# Port_Expander.net
KiCad netlist of a schematic drawn in Altium Designer
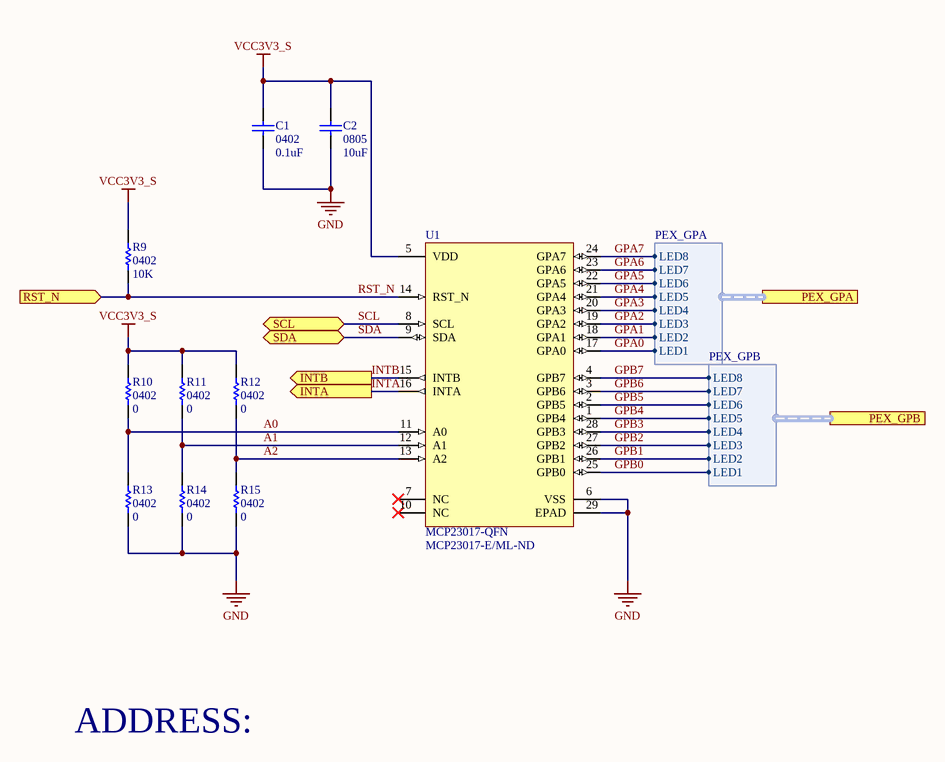
[diagram p0: Port Expander.SchDoc]

(export (version "E")
  (design (tool "Eeschema 10.0.6"))
  (components
    (comp (ref "C1")
      (value "0402")
      (footprint "CAP0402R")
      (description "0402 capacitor")
      (fields
        (field (name "ALTIUM_VALUE") "0.1uF")
        (field (name "MANUFACTURER") "Taiyo Yuden")
        (field (name "MANUFACTURER PART NUMBER") "EMK105B7104KVHF")
      )
      (libsource (lib "heron-general") (part "CAP0402"))
    )
    (comp (ref "C2")
      (value "0805")
      (footprint "CAP0805R")
      (description "0805 capacitor")
      (fields
        (field (name "ALTIUM_VALUE") "10uF")
        (field (name "MANUFACTURER") "Murata")
        (field (name "MANUFACTURER PART NUMBER") "GCM21BR70J106KE22K")
      )
      (libsource (lib "heron-general") (part "CAP0805"))
    )
    (comp (ref "R9")
      (value "0402")
      (footprint "RES0402R")
      (description "0402 resistor")
      (fields
        (field (name "ALTIUM_VALUE") "10K")
        (field (name "MANUFACTURER") "Panasonic")
        (field (name "MANUFACTURER PART NUMBER") "ERJ-2RKF1002X")
      )
      (libsource (lib "heron-general") (part "RES0402"))
    )
    (comp (ref "R10")
      (value "0402")
      (footprint "RES0402R")
      (description "0402 resistor")
      (fields
        (field (name "ALTIUM_VALUE") "0")
        (field (name "MANUFACTURER") "Panasonic")
        (field (name "MANUFACTURER PART NUMBER") "ERJ-2GE0R00X")
      )
      (libsource (lib "heron-general") (part "RES0402"))
    )
    (comp (ref "R11")
      (value "0402")
      (footprint "RES0402R")
      (description "0402 resistor")
      (fields
        (field (name "ALTIUM_VALUE") "0")
        (field (name "MANUFACTURER") "Panasonic")
        (field (name "MANUFACTURER PART NUMBER") "ERJ-2GE0R00X")
      )
      (libsource (lib "heron-general") (part "RES0402"))
    )
    (comp (ref "R12")
      (value "0402")
      (footprint "RES0402R")
      (description "0402 resistor")
      (fields
        (field (name "ALTIUM_VALUE") "0")
        (field (name "MANUFACTURER") "Panasonic")
        (field (name "MANUFACTURER PART NUMBER") "ERJ-2GE0R00X")
      )
      (libsource (lib "heron-general") (part "RES0402"))
    )
    (comp (ref "R13")
      (value "0402")
      (footprint "RES0402R")
      (description "0402 resistor")
      (fields
        (field (name "ALTIUM_VALUE") "0")
        (field (name "MANUFACTURER") "Panasonic")
        (field (name "MANUFACTURER PART NUMBER") "ERJ-2GE0R00X")
      )
      (libsource (lib "heron-general") (part "RES0402"))
    )
    (comp (ref "R14")
      (value "0402")
      (footprint "RES0402R")
      (description "0402 resistor")
      (fields
        (field (name "ALTIUM_VALUE") "0")
        (field (name "MANUFACTURER") "Panasonic")
        (field (name "MANUFACTURER PART NUMBER") "ERJ-2GE0R00X")
      )
      (libsource (lib "heron-general") (part "RES0402"))
    )
    (comp (ref "R15")
      (value "0402")
      (footprint "RES0402R")
      (description "0402 resistor")
      (fields
        (field (name "ALTIUM_VALUE") "0")
        (field (name "MANUFACTURER") "Panasonic")
        (field (name "MANUFACTURER PART NUMBER") "ERJ-2GE0R00X")
      )
      (libsource (lib "heron-general") (part "RES0402"))
    )
    (comp (ref "U1")
      (value "MCP23017-QFN")
      (footprint "QFN65P600X600X100-29")
      (fields (field (name "SUPPLIER PART NUMBER 1") "MCP23017-E/ML-ND"))
      (libsource (lib "heron-general") (part "MCP23017-QFN"))
    )
  )
  (nets
    (net (code "3") (name "/A0") (class "Default")
      (node (ref "R10") (pin "1") (pinfunction "1_1") (pintype "passive"))
      (node (ref "R13") (pin "2") (pinfunction "2_2") (pintype "passive"))
      (node (ref "U1") (pin "11") (pinfunction "A0_11") (pintype "input"))
    )
    (net (code "4") (name "/A1") (class "Default")
      (node (ref "R11") (pin "1") (pinfunction "1_1") (pintype "passive"))
      (node (ref "R14") (pin "2") (pinfunction "2_2") (pintype "passive"))
      (node (ref "U1") (pin "12") (pinfunction "A1_12") (pintype "input"))
    )
    (net (code "5") (name "/A2") (class "Default")
      (node (ref "R12") (pin "1") (pinfunction "1_1") (pintype "passive"))
      (node (ref "R15") (pin "2") (pinfunction "2_2") (pintype "passive"))
      (node (ref "U1") (pin "13") (pinfunction "A2_13") (pintype "input"))
    )
    (net (code "6") (name "/GPA0") (class "Default")
      (node (ref "U1") (pin "17") (pinfunction "GPA0_17") (pintype "bidirectional"))
    )
    (net (code "7") (name "/GPA1") (class "Default")
      (node (ref "U1") (pin "18") (pinfunction "GPA1_18") (pintype "bidirectional"))
    )
    (net (code "8") (name "/GPA2") (class "Default")
      (node (ref "U1") (pin "19") (pinfunction "GPA2_19") (pintype "bidirectional"))
    )
    (net (code "9") (name "/GPA3") (class "Default")
      (node (ref "U1") (pin "20") (pinfunction "GPA3_20") (pintype "bidirectional"))
    )
    (net (code "10") (name "/GPA4") (class "Default")
      (node (ref "U1") (pin "21") (pinfunction "GPA4_21") (pintype "bidirectional"))
    )
    (net (code "11") (name "/GPA5") (class "Default")
      (node (ref "U1") (pin "22") (pinfunction "GPA5_22") (pintype "bidirectional"))
    )
    (net (code "12") (name "/GPA6") (class "Default")
      (node (ref "U1") (pin "23") (pinfunction "GPA6_23") (pintype "bidirectional"))
    )
    (net (code "13") (name "/GPA7") (class "Default")
      (node (ref "U1") (pin "24") (pinfunction "GPA7_24") (pintype "bidirectional"))
    )
    (net (code "14") (name "/GPB0") (class "Default")
      (node (ref "U1") (pin "25") (pinfunction "GPB0_25") (pintype "bidirectional"))
    )
    (net (code "15") (name "/GPB1") (class "Default")
      (node (ref "U1") (pin "26") (pinfunction "GPB1_26") (pintype "bidirectional"))
    )
    (net (code "16") (name "/GPB2") (class "Default")
      (node (ref "U1") (pin "27") (pinfunction "GPB2_27") (pintype "bidirectional"))
    )
    (net (code "17") (name "/GPB3") (class "Default")
      (node (ref "U1") (pin "28") (pinfunction "GPB3_28") (pintype "bidirectional"))
    )
    (net (code "18") (name "/GPB4") (class "Default")
      (node (ref "U1") (pin "1") (pinfunction "GPB4_1") (pintype "bidirectional"))
    )
    (net (code "19") (name "/GPB5") (class "Default")
      (node (ref "U1") (pin "2") (pinfunction "GPB5_2") (pintype "bidirectional"))
    )
    (net (code "20") (name "/GPB6") (class "Default")
      (node (ref "U1") (pin "3") (pinfunction "GPB6_3") (pintype "bidirectional"))
    )
    (net (code "21") (name "/GPB7") (class "Default")
      (node (ref "U1") (pin "4") (pinfunction "GPB7_4") (pintype "bidirectional"))
    )
    (net (code "22") (name "/INTA") (class "Default")
      (node (ref "U1") (pin "16") (pinfunction "INTA_16") (pintype "output"))
    )
    (net (code "23") (name "/INTB") (class "Default")
      (node (ref "U1") (pin "15") (pinfunction "INTB_15") (pintype "output"))
    )
    (net (code "24") (name "/RST_N") (class "Default")
      (node (ref "R9") (pin "1") (pinfunction "1_1") (pintype "passive"))
      (node (ref "U1") (pin "14") (pinfunction "RST_N_14") (pintype "input"))
    )
    (net (code "25") (name "/SCL") (class "Default")
      (node (ref "U1") (pin "8") (pinfunction "SCL_8") (pintype "input"))
    )
    (net (code "26") (name "/SDA") (class "Default")
      (node (ref "U1") (pin "9") (pinfunction "SDA_9") (pintype "bidirectional"))
    )
    (net (code "29") (name "GND") (class "Default")
      (node (ref "C1") (pin "1") (pinfunction "1_1") (pintype "passive"))
      (node (ref "C2") (pin "1") (pinfunction "1_1") (pintype "passive"))
      (node (ref "R13") (pin "1") (pinfunction "1_1") (pintype "passive"))
      (node (ref "R14") (pin "1") (pinfunction "1_1") (pintype "passive"))
      (node (ref "R15") (pin "1") (pinfunction "1_1") (pintype "passive"))
      (node (ref "U1") (pin "29") (pinfunction "EPAD_29") (pintype "power_in"))
      (node (ref "U1") (pin "6") (pinfunction "VSS_6") (pintype "power_in"))
    )
    (net (code "30") (name "VCC3V3_S") (class "Default")
      (node (ref "C1") (pin "2") (pinfunction "2_2") (pintype "passive"))
      (node (ref "C2") (pin "2") (pinfunction "2_2") (pintype "passive"))
      (node (ref "R10") (pin "2") (pinfunction "2_2") (pintype "passive"))
      (node (ref "R11") (pin "2") (pinfunction "2_2") (pintype "passive"))
      (node (ref "R12") (pin "2") (pinfunction "2_2") (pintype "passive"))
      (node (ref "R9") (pin "2") (pinfunction "2_2") (pintype "passive"))
      (node (ref "U1") (pin "5") (pinfunction "VDD_5") (pintype "power_in"))
    )
    (net (code "31") (name "unconnected-(U1-NC-Pad7)") (class "Default")
      (node (ref "U1") (pin "7") (pinfunction "NC_7") (pintype "passive+no_connect"))
    )
    (net (code "32") (name "unconnected-(U1-NC-Pad10)") (class "Default")
      (node (ref "U1") (pin "10") (pinfunction "NC_10") (pintype "passive+no_connect"))
    )
  )
)
